# PIC.net
KiCad netlist of a schematic drawn in Altium Designer
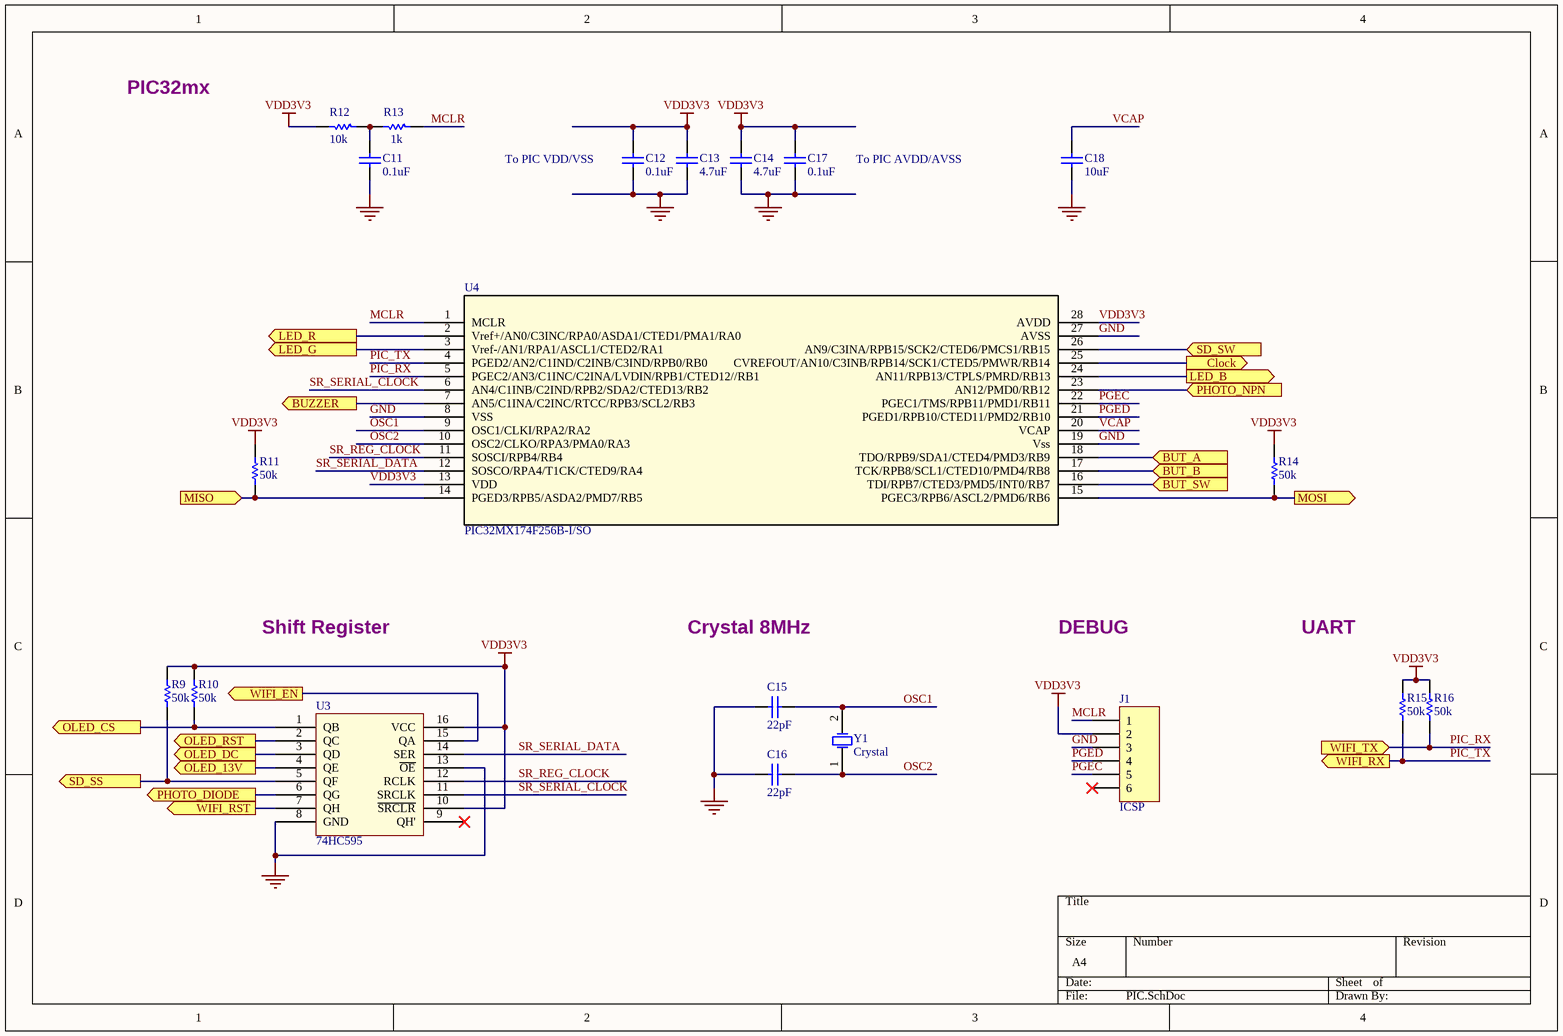
[diagram p0: PIC.SchDoc]

(export (version "E")
  (design (tool "Eeschema 10.0.6"))
  (components
    (comp (ref "C11")
      (value "0.1uF")
      (footprint "CAPC1608X90N")
      (description "Ceramic")
      (libsource (lib "POP_lib") (part "Capacitor"))
    )
    (comp (ref "C12")
      (value "0.1uF")
      (footprint "CAPC1608X90N")
      (description "Ceramic")
      (libsource (lib "POP_lib") (part "Capacitor"))
    )
    (comp (ref "C13")
      (value "4.7uF")
      (footprint "CAPC1608X90N")
      (description "Ceramic")
      (libsource (lib "POP_lib") (part "Capacitor"))
    )
    (comp (ref "C14")
      (value "4.7uF")
      (footprint "CAPC1608X90N")
      (description "Ceramic")
      (libsource (lib "POP_lib") (part "Capacitor"))
    )
    (comp (ref "C15")
      (value "22pF")
      (footprint "CAPC1608X90N")
      (description "Capacitor")
      (libsource (lib "POP_lib") (part "Capacitor"))
    )
    (comp (ref "C16")
      (value "22pF")
      (footprint "CAPC1608X90N")
      (description "Capacitor")
      (libsource (lib "POP_lib") (part "Capacitor"))
    )
    (comp (ref "C17")
      (value "0.1uF")
      (footprint "CAPC1608X90N")
      (description "Ceramic")
      (libsource (lib "POP_lib") (part "Capacitor"))
    )
    (comp (ref "C18")
      (value "10uF")
      (footprint "CAPC1608X90N")
      (description "Capacitor")
      (libsource (lib "POP_lib") (part "Capacitor"))
    )
    (comp (ref "J1")
      (value "ICSP")
      (footprint "ICSP_HEADER")
      (description "Header, 6-Pin")
      (libsource (lib "POP_lib") (part "Header 6"))
    )
    (comp (ref "R9")
      (value "50k")
      (footprint "RESC1608X55N")
      (description "Resistor")
      (fields (field (name "PUBLISHER") "Altium Limited"))
      (libsource (lib "POP_lib") (part "Resistor"))
    )
    (comp (ref "R10")
      (value "50k")
      (footprint "RESC1608X55N")
      (description "Resistor")
      (fields (field (name "PUBLISHER") "Altium Limited"))
      (libsource (lib "POP_lib") (part "Resistor"))
    )
    (comp (ref "R11")
      (value "50k")
      (footprint "RESC1608X55N")
      (description "Resistor")
      (libsource (lib "POP_lib") (part "Resistor"))
    )
    (comp (ref "R12")
      (value "10k")
      (footprint "RESC1608X55N")
      (description "Resistor")
      (libsource (lib "POP_lib") (part "Resistor"))
    )
    (comp (ref "R13") (value "1k") (footprint "RESC1608X55N") (libsource (lib "POP_lib") (part "Resistor")))
    (comp (ref "R14")
      (value "50k")
      (footprint "RESC1608X55N")
      (description "Resistor")
      (libsource (lib "POP_lib") (part "Resistor"))
    )
    (comp (ref "R15")
      (value "50k")
      (footprint "RESC1608X55N")
      (description "Resistor")
      (libsource (lib "POP_lib") (part "Resistor"))
    )
    (comp (ref "R16")
      (value "50k")
      (footprint "RESC1608X55N")
      (description "Resistor")
      (libsource (lib "POP_lib") (part "Resistor"))
    )
    (comp (ref "U3")
      (value "74HC595")
      (footprint "SOIC-16")
      (description "Shift Register")
      (libsource (lib "POP_lib") (part "74HC595"))
    )
    (comp (ref "U4")
      (value "PIC32MX174F256B-I/SO")
      (footprint "SOIC-28")
      (description "PIC32")
      (libsource (lib "POP_lib") (part "PIC32MX174F256B-I/SO"))
    )
    (comp (ref "Y1")
      (value "Crystal")
      (footprint "9C")
      (description "Crystal Oscillator")
      (libsource (lib "POP_lib") (part "Crystal"))
    )
  )
  (nets
    (net (code "1") (name "/BUT_A") (class "Default")
      (node (ref "U4") (pin "18") (pinfunction "TDO/RPB9/SDA1/CTED4/PMD3/RB9_18") (pintype "passive"))
    )
    (net (code "2") (name "/BUT_B") (class "Default")
      (node (ref "U4") (pin "17") (pinfunction "TCK/RPB8/SCL1/CTED10/PMD4/RB8_17") (pintype "passive"))
    )
    (net (code "3") (name "/BUT_SW") (class "Default")
      (node (ref "U4") (pin "16") (pinfunction "TDI/RPB7/CTED3/PMD5/INT0/RB7_16") (pintype "passive"))
    )
    (net (code "4") (name "/BUZZER") (class "Default")
      (node (ref "U4") (pin "7") (pinfunction "AN5/C1INA/C2INC/RTCC/RPB3/SCL2/RB3_7") (pintype "passive"))
    )
    (net (code "5") (name "/Clock") (class "Default")
      (node (ref "U4") (pin "25") (pinfunction "CVREFOUT/AN10/C3INB/RPB14/SCK1/CTED5/PMWR/RB14_25") (pintype "passive"))
    )
    (net (code "6") (name "/LED_B") (class "Default")
      (node (ref "U4") (pin "24") (pinfunction "AN11/RPB13/CTPLS/PMRD/RB13_24") (pintype "passive"))
    )
    (net (code "7") (name "/LED_G") (class "Default")
      (node (ref "U4") (pin "3") (pinfunction "Vref-/AN1/RPA1/ASCL1/CTED2/RA1_3") (pintype "passive"))
    )
    (net (code "8") (name "/LED_R") (class "Default")
      (node (ref "U4") (pin "2") (pinfunction "Vref+/AN0/C3INC/RPA0/ASDA1/CTED1/PMA1/RA0_2") (pintype "passive"))
    )
    (net (code "9") (name "/MCLR") (class "Default")
      (node (ref "J1") (pin "1") (pinfunction "1_1") (pintype "passive"))
      (node (ref "R13") (pin "1") (pinfunction "1_1") (pintype "passive"))
      (node (ref "U4") (pin "1") (pinfunction "MCLR_1") (pintype "passive"))
    )
    (net (code "10") (name "/MISO") (class "Default")
      (node (ref "R11") (pin "1") (pinfunction "1_1") (pintype "passive"))
      (node (ref "U4") (pin "14") (pinfunction "PGED3/RPB5/ASDA2/PMD7/RB5_14") (pintype "passive"))
    )
    (net (code "11") (name "/MOSI") (class "Default")
      (node (ref "R14") (pin "1") (pinfunction "1_1") (pintype "passive"))
      (node (ref "U4") (pin "15") (pinfunction "PGEC3/RPB6/ASCL2/PMD6/RB6_15") (pintype "passive"))
    )
    (net (code "12") (name "/OLED_13V") (class "Default")
      (node (ref "U3") (pin "4") (pinfunction "QE_4") (pintype "passive"))
    )
    (net (code "13") (name "/OLED_CS") (class "Default")
      (node (ref "R10") (pin "1") (pinfunction "1_1") (pintype "passive"))
      (node (ref "U3") (pin "1") (pinfunction "QB_1") (pintype "passive"))
    )
    (net (code "14") (name "/OLED_DC") (class "Default")
      (node (ref "U3") (pin "3") (pinfunction "QD_3") (pintype "passive"))
    )
    (net (code "15") (name "/OLED_RST") (class "Default")
      (node (ref "U3") (pin "2") (pinfunction "QC_2") (pintype "passive"))
    )
    (net (code "16") (name "/OSC1") (class "Default")
      (node (ref "C15") (pin "1") (pinfunction "1_1") (pintype "passive"))
      (node (ref "U4") (pin "9") (pinfunction "OSC1/CLKI/RPA2/RA2_9") (pintype "passive"))
      (node (ref "Y1") (pin "2") (pinfunction "2_2") (pintype "passive"))
    )
    (net (code "17") (name "/OSC2") (class "Default")
      (node (ref "C16") (pin "1") (pinfunction "1_1") (pintype "passive"))
      (node (ref "U4") (pin "10") (pinfunction "OSC2/CLKO/RPA3/PMA0/RA3_10") (pintype "passive"))
      (node (ref "Y1") (pin "1") (pinfunction "1_1") (pintype "passive"))
    )
    (net (code "18") (name "/PGEC") (class "Default")
      (node (ref "J1") (pin "5") (pinfunction "5_5") (pintype "passive"))
      (node (ref "U4") (pin "22") (pinfunction "PGEC1/TMS/RPB11/PMD1/RB11_22") (pintype "passive"))
    )
    (net (code "19") (name "/PGED") (class "Default")
      (node (ref "J1") (pin "4") (pinfunction "4_4") (pintype "passive"))
      (node (ref "U4") (pin "21") (pinfunction "PGED1/RPB10/CTED11/PMD2/RB10_21") (pintype "passive"))
    )
    (net (code "20") (name "/PHOTO_DIODE") (class "Default")
      (node (ref "U3") (pin "6") (pinfunction "QG_6") (pintype "passive"))
    )
    (net (code "21") (name "/PHOTO_NPN") (class "Default")
      (node (ref "U4") (pin "23") (pinfunction "AN12/PMD0/RB12_23") (pintype "passive"))
    )
    (net (code "22") (name "/PIC_RX") (class "Default")
      (node (ref "R16") (pin "1") (pinfunction "1_1") (pintype "passive"))
      (node (ref "U4") (pin "5") (pinfunction "PGEC2/AN3/C1INC/C2INA/LVDIN/RPB1/CTED12//RB1_5") (pintype "passive"))
    )
    (net (code "23") (name "/PIC_TX") (class "Default")
      (node (ref "R15") (pin "1") (pinfunction "1_1") (pintype "passive"))
      (node (ref "U4") (pin "4") (pinfunction "PGED2/AN2/C1IND/C2INB/C3IND/RPB0/RB0_4") (pintype "passive"))
    )
    (net (code "24") (name "/SD_SS") (class "Default")
      (node (ref "R9") (pin "1") (pinfunction "1_1") (pintype "passive"))
      (node (ref "U3") (pin "5") (pinfunction "QF_5") (pintype "passive"))
    )
    (net (code "25") (name "/SD_SW") (class "Default")
      (node (ref "U4") (pin "26") (pinfunction "AN9/C3INA/RPB15/SCK2/CTED6/PMCS1/RB15_26") (pintype "passive"))
    )
    (net (code "26") (name "/SR_REG_CLOCK") (class "Default")
      (node (ref "U3") (pin "12") (pinfunction "RCLK_12") (pintype "passive"))
      (node (ref "U4") (pin "11") (pinfunction "SOSCI/RPB4/RB4_11") (pintype "passive"))
    )
    (net (code "27") (name "/SR_SERIAL_CLOCK") (class "Default")
      (node (ref "U3") (pin "11") (pinfunction "SRCLK_11") (pintype "passive"))
      (node (ref "U4") (pin "6") (pinfunction "AN4/C1INB/C2IND/RPB2/SDA2/CTED13/RB2_6") (pintype "passive"))
    )
    (net (code "28") (name "/SR_SERIAL_DATA") (class "Default")
      (node (ref "U3") (pin "14") (pinfunction "SER_14") (pintype "passive"))
      (node (ref "U4") (pin "12") (pinfunction "SOSCO/RPA4/T1CK/CTED9/RA4_12") (pintype "passive"))
    )
    (net (code "29") (name "/VCAP") (class "Default")
      (node (ref "C18") (pin "2") (pinfunction "2_2") (pintype "passive"))
      (node (ref "U4") (pin "20") (pinfunction "VCAP_20") (pintype "passive"))
    )
    (net (code "30") (name "/WIFI_EN") (class "Default")
      (node (ref "U3") (pin "15") (pinfunction "QA_15") (pintype "passive"))
    )
    (net (code "31") (name "/WIFI_RST") (class "Default")
      (node (ref "U3") (pin "7") (pinfunction "QH_7") (pintype "passive"))
    )
    (net (code "32") (name "GND") (class "Default")
      (node (ref "C11") (pin "1") (pinfunction "1_1") (pintype "passive"))
      (node (ref "C12") (pin "1") (pinfunction "1_1") (pintype "passive"))
      (node (ref "C13") (pin "1") (pinfunction "1_1") (pintype "passive"))
      (node (ref "C14") (pin "1") (pinfunction "1_1") (pintype "passive"))
      (node (ref "C15") (pin "2") (pinfunction "2_2") (pintype "passive"))
      (node (ref "C16") (pin "2") (pinfunction "2_2") (pintype "passive"))
      (node (ref "C17") (pin "1") (pinfunction "1_1") (pintype "passive"))
      (node (ref "C18") (pin "1") (pinfunction "1_1") (pintype "passive"))
      (node (ref "J1") (pin "3") (pinfunction "3_3") (pintype "passive"))
      (node (ref "U3") (pin "13") (pinfunction "~{OE}_13") (pintype "passive"))
      (node (ref "U3") (pin "8") (pinfunction "GND_8") (pintype "passive"))
      (node (ref "U4") (pin "19") (pinfunction "Vss_19") (pintype "passive"))
      (node (ref "U4") (pin "27") (pinfunction "AVSS_27") (pintype "passive"))
      (node (ref "U4") (pin "8") (pinfunction "VSS_8") (pintype "passive"))
    )
    (net (code "33") (name "Net-(C11-Pad2)") (class "Default")
      (node (ref "C11") (pin "2") (pinfunction "2_2") (pintype "passive"))
      (node (ref "R12") (pin "1") (pinfunction "1_1") (pintype "passive"))
      (node (ref "R13") (pin "2") (pinfunction "2_2") (pintype "passive"))
    )
    (net (code "34") (name "VDD3V3") (class "Default")
      (node (ref "C12") (pin "2") (pinfunction "2_2") (pintype "passive"))
      (node (ref "C13") (pin "2") (pinfunction "2_2") (pintype "passive"))
      (node (ref "C14") (pin "2") (pinfunction "2_2") (pintype "passive"))
      (node (ref "C17") (pin "2") (pinfunction "2_2") (pintype "passive"))
      (node (ref "J1") (pin "2") (pinfunction "2_2") (pintype "passive"))
      (node (ref "R10") (pin "2") (pinfunction "2_2") (pintype "passive"))
      (node (ref "R11") (pin "2") (pinfunction "2_2") (pintype "passive"))
      (node (ref "R12") (pin "2") (pinfunction "2_2") (pintype "passive"))
      (node (ref "R14") (pin "2") (pinfunction "2_2") (pintype "passive"))
      (node (ref "R15") (pin "2") (pinfunction "2_2") (pintype "passive"))
      (node (ref "R16") (pin "2") (pinfunction "2_2") (pintype "passive"))
      (node (ref "R9") (pin "2") (pinfunction "2_2") (pintype "passive"))
      (node (ref "U3") (pin "10") (pinfunction "~{SRCLR}_10") (pintype "passive"))
      (node (ref "U3") (pin "16") (pinfunction "VCC_16") (pintype "passive"))
      (node (ref "U4") (pin "13") (pinfunction "VDD_13") (pintype "passive"))
      (node (ref "U4") (pin "28") (pinfunction "AVDD_28") (pintype "passive"))
    )
    (net (code "35") (name "unconnected-(J1-Pad6)") (class "Default")
      (node (ref "J1") (pin "6") (pinfunction "6_6") (pintype "passive+no_connect"))
    )
    (net (code "36") (name "unconnected-(U3-QH'-Pad9)") (class "Default")
      (node (ref "U3") (pin "9") (pinfunction "QH'_9") (pintype "passive+no_connect"))
    )
  )
)
